# photonAlarm4.net
KiCad netlist of a schematic drawn in EAGLE
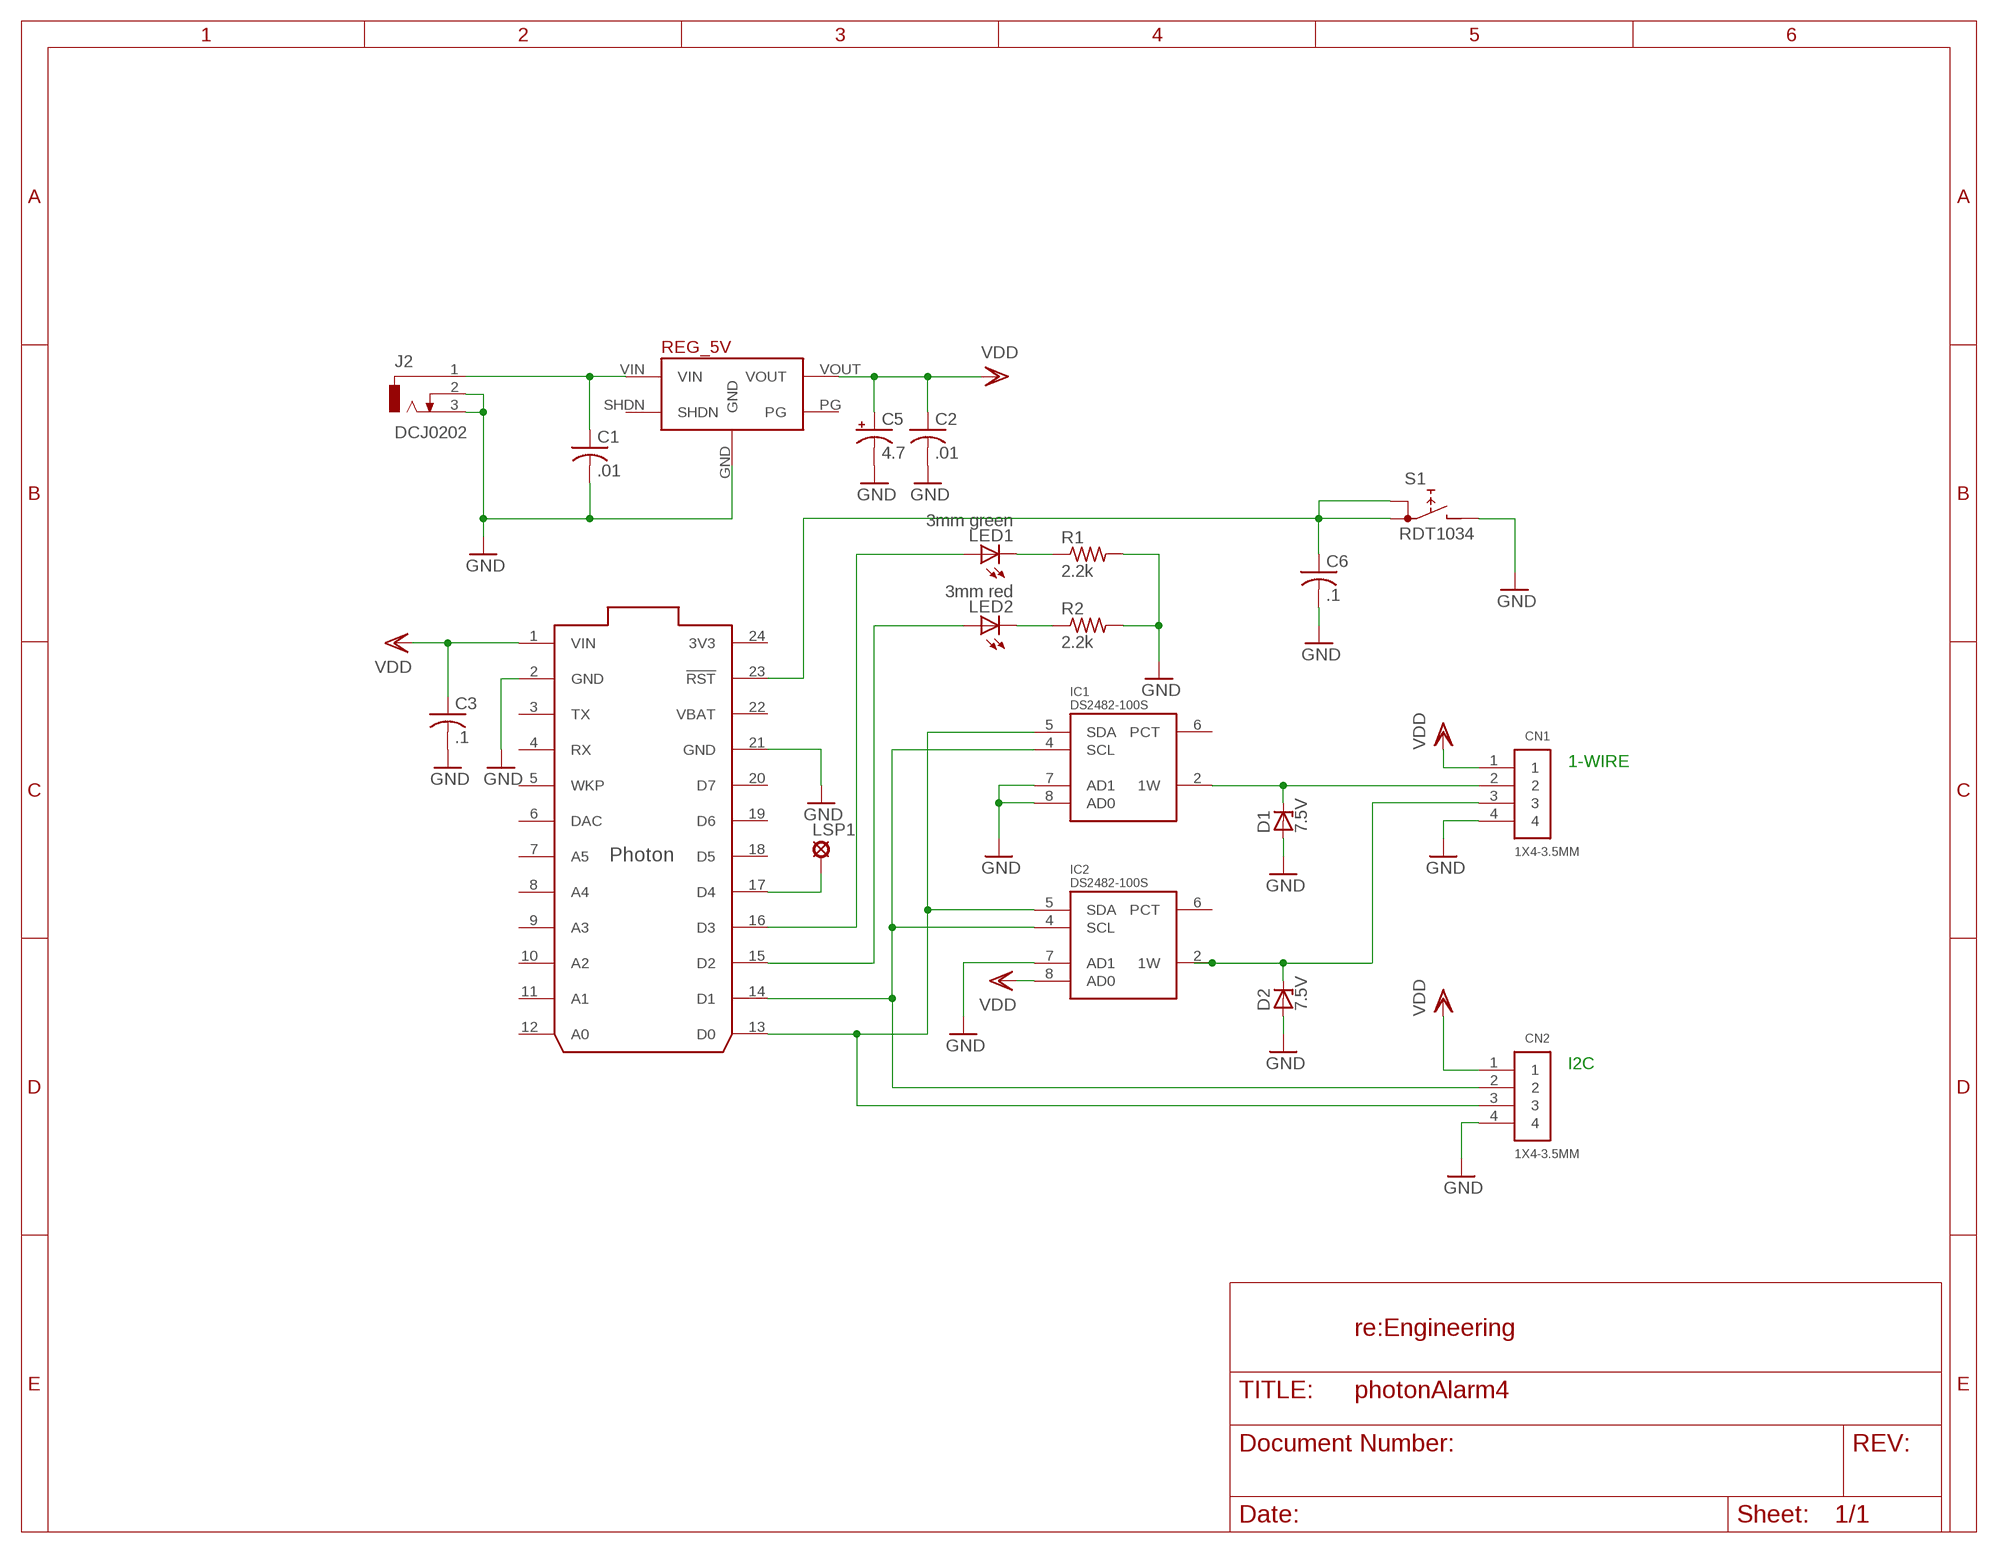
[diagram p0: schematic, sheet 1]

(export (version "E")
  (design (tool "Eeschema 10.0.6"))
  (components
    (comp (ref "C1")
      (value ".01")
      (footprint "eagle-import:C0805")
      (libsource (lib "eagle-import") (part "C-USC0805"))
    )
    (comp (ref "C2")
      (value ".01")
      (footprint "eagle-import:C0805")
      (libsource (lib "eagle-import") (part "C-USC0805"))
    )
    (comp (ref "C3")
      (value ".1")
      (footprint "eagle-import:C0805")
      (libsource (lib "eagle-import") (part "C-USC0805"))
    )
    (comp (ref "C5")
      (value "4.7")
      (footprint "eagle-import:E5-6")
      (libsource (lib "eagle-import") (part "CPOL-USE5-6"))
    )
    (comp (ref "C6")
      (value ".1")
      (footprint "eagle-import:C0805")
      (libsource (lib "eagle-import") (part "C-USC0805"))
    )
    (comp (ref "CN1")
      (value "1X4-3.5MM")
      (footprint "eagle-import:1X04-3.5MM")
      (libsource (lib "eagle-import") (part "1X4-3.5MM"))
    )
    (comp (ref "CN2")
      (value "1X4-3.5MM")
      (footprint "eagle-import:1X04-3.5MM")
      (libsource (lib "eagle-import") (part "1X4-3.5MM"))
    )
    (comp (ref "D1")
      (value "7.5V")
      (footprint "eagle-import:ZDIO-5")
      (libsource (lib "eagle-import") (part "ZENER-DIODEZD-5"))
    )
    (comp (ref "D2")
      (value "7.5V")
      (footprint "eagle-import:ZDIO-5")
      (libsource (lib "eagle-import") (part "ZENER-DIODEZD-5"))
    )
    (comp (ref "IC1")
      (value "DS2482-100S")
      (footprint "eagle-import:SO08")
      (libsource (lib "eagle-import") (part "DS2482-100S"))
    )
    (comp (ref "IC2")
      (value "DS2482-100S")
      (footprint "eagle-import:SO08")
      (libsource (lib "eagle-import") (part "DS2482-100S"))
    )
    (comp (ref "J2")
      (value "DCJ0202")
      (footprint "eagle-import:DCJ0202")
      (libsource (lib "eagle-import") (part "DCJ0202"))
    )
    (comp (ref "LED1")
      (value "3mm green")
      (footprint "eagle-import:LED5MM")
      (libsource (lib "eagle-import") (part "LED5MM"))
    )
    (comp (ref "LED2")
      (value "3mm red")
      (footprint "eagle-import:LED5MM")
      (libsource (lib "eagle-import") (part "LED5MM"))
    )
    (comp (ref "LSP1")
      (value "LSP10")
      (footprint "eagle-import:LSP10")
      (libsource (lib "eagle-import") (part "LSP10"))
    )
    (comp (ref "R1")
      (value "2.2k")
      (footprint "eagle-import:M0805")
      (libsource (lib "eagle-import") (part "R-US_M0805"))
    )
    (comp (ref "R2")
      (value "2.2k")
      (footprint "eagle-import:M0805")
      (libsource (lib "eagle-import") (part "R-US_M0805"))
    )
    (comp (ref "REG_5V")
      (value "5V_D24V10FA")
      (footprint "eagle-import:5V_D24V10F5")
      (libsource (lib "eagle-import") (part "5V_D24V10FA"))
    )
    (comp (ref "S1")
      (value "RDT1034")
      (footprint "eagle-import:RDT1034")
      (libsource (lib "eagle-import") (part "RDT1034"))
    )
    (comp (ref "U$1")
      (value "PHOTON_WITH_HEADERS")
      (footprint "eagle-import:PHOTON")
      (libsource (lib "eagle-import") (part "PHOTON_WITH_HEADERS"))
    )
  )
  (nets
    (net (code "1") (name "/3V3") (class "Default")
      (node (ref "U$1") (pin "24") (pinfunction "3V3_24") (pintype "power_in"))
    )
    (net (code "2") (name "/VBAT") (class "Default")
      (node (ref "U$1") (pin "22") (pinfunction "VBAT_22") (pintype "power_in"))
    )
    (net (code "3") (name "GND") (class "Default")
      (node (ref "C1") (pin "2") (pinfunction "2_2") (pintype "passive"))
      (node (ref "C2") (pin "2") (pinfunction "2_2") (pintype "passive"))
      (node (ref "C3") (pin "2") (pinfunction "2_2") (pintype "passive"))
      (node (ref "C5") (pin "-") (pinfunction "-_-") (pintype "passive"))
      (node (ref "C6") (pin "2") (pinfunction "2_2") (pintype "passive"))
      (node (ref "CN1") (pin "4") (pinfunction "4_4") (pintype "bidirectional"))
      (node (ref "CN2") (pin "4") (pinfunction "4_4") (pintype "bidirectional"))
      (node (ref "D1") (pin "A") (pinfunction "A_A") (pintype "passive"))
      (node (ref "D2") (pin "A") (pinfunction "A_A") (pintype "passive"))
      (node (ref "IC1") (pin "7") (pinfunction "AD1_7") (pintype "input"))
      (node (ref "IC1") (pin "8") (pinfunction "AD0_8") (pintype "input"))
      (node (ref "IC2") (pin "7") (pinfunction "AD1_7") (pintype "input"))
      (node (ref "J2") (pin "2") (pinfunction "2_2") (pintype "passive"))
      (node (ref "J2") (pin "3") (pinfunction "3_3") (pintype "passive"))
      (node (ref "R1") (pin "2") (pinfunction "2_2") (pintype "passive"))
      (node (ref "R2") (pin "2") (pinfunction "2_2") (pintype "passive"))
      (node (ref "REG_5V") (pin "GND") (pinfunction "GND_GND") (pintype "bidirectional"))
      (node (ref "S1") (pin "B") (pinfunction "B_B") (pintype "passive"))
      (node (ref "U$1") (pin "2") (pinfunction "GND_2") (pintype "power_in"))
      (node (ref "U$1") (pin "21") (pinfunction "GND_21") (pintype "power_in"))
    )
    (net (code "4") (name "Net-(C1-Pad1)") (class "Default")
      (node (ref "C1") (pin "1") (pinfunction "1_1") (pintype "passive"))
      (node (ref "J2") (pin "1") (pinfunction "1_1") (pintype "passive"))
      (node (ref "REG_5V") (pin "VIN") (pinfunction "VIN_VIN") (pintype "bidirectional"))
    )
    (net (code "5") (name "Net-(IC1A-1W)") (class "Default")
      (node (ref "CN1") (pin "2") (pinfunction "2_2") (pintype "bidirectional"))
      (node (ref "D1") (pin "C") (pinfunction "C_C") (pintype "passive"))
      (node (ref "IC1") (pin "2") (pinfunction "1W_2") (pintype "open_collector"))
    )
    (net (code "6") (name "Net-(IC1A-SCL)") (class "Default")
      (node (ref "CN2") (pin "2") (pinfunction "2_2") (pintype "bidirectional"))
      (node (ref "IC1") (pin "4") (pinfunction "SCL_4") (pintype "input"))
      (node (ref "IC2") (pin "4") (pinfunction "SCL_4") (pintype "input"))
      (node (ref "U$1") (pin "14") (pinfunction "D1_14") (pintype "bidirectional"))
    )
    (net (code "7") (name "Net-(IC1A-SDA)") (class "Default")
      (node (ref "CN2") (pin "3") (pinfunction "3_3") (pintype "bidirectional"))
      (node (ref "IC1") (pin "5") (pinfunction "SDA_5") (pintype "bidirectional"))
      (node (ref "IC2") (pin "5") (pinfunction "SDA_5") (pintype "bidirectional"))
      (node (ref "U$1") (pin "13") (pinfunction "D0_13") (pintype "bidirectional"))
    )
    (net (code "8") (name "Net-(IC2A-1W)") (class "Default")
      (node (ref "CN1") (pin "3") (pinfunction "3_3") (pintype "bidirectional"))
      (node (ref "D2") (pin "C") (pinfunction "C_C") (pintype "passive"))
      (node (ref "IC2") (pin "2") (pinfunction "1W_2") (pintype "open_collector"))
    )
    (net (code "9") (name "Net-(LED1-C)") (class "Default")
      (node (ref "LED1") (pin "K") (pinfunction "C_K") (pintype "passive"))
      (node (ref "R1") (pin "1") (pinfunction "1_1") (pintype "passive"))
    )
    (net (code "10") (name "Net-(LED2-C)") (class "Default")
      (node (ref "LED2") (pin "K") (pinfunction "C_K") (pintype "passive"))
      (node (ref "R2") (pin "1") (pinfunction "1_1") (pintype "passive"))
    )
    (net (code "11") (name "Net-(U$1-D2)") (class "Default")
      (node (ref "LED2") (pin "A") (pinfunction "A_A") (pintype "passive"))
      (node (ref "U$1") (pin "15") (pinfunction "D2_15") (pintype "bidirectional"))
    )
    (net (code "12") (name "Net-(U$1-D3)") (class "Default")
      (node (ref "LED1") (pin "A") (pinfunction "A_A") (pintype "passive"))
      (node (ref "U$1") (pin "16") (pinfunction "D3_16") (pintype "bidirectional"))
    )
    (net (code "13") (name "Net-(U$1-D4)") (class "Default")
      (node (ref "LSP1") (pin "MP") (pinfunction "MP_MP") (pintype "passive"))
      (node (ref "U$1") (pin "17") (pinfunction "D4_17") (pintype "bidirectional"))
    )
    (net (code "14") (name "Net-(U$1-~{RST})") (class "Default")
      (node (ref "C6") (pin "1") (pinfunction "1_1") (pintype "passive"))
      (node (ref "S1") (pin "A") (pinfunction "A_A") (pintype "passive"))
      (node (ref "S1") (pin "A1") (pinfunction "A1_A1") (pintype "passive"))
      (node (ref "U$1") (pin "23") (pinfunction "~{RST}_23") (pintype "bidirectional"))
    )
    (net (code "15") (name "VDD") (class "Default")
      (node (ref "C2") (pin "1") (pinfunction "1_1") (pintype "passive"))
      (node (ref "C3") (pin "1") (pinfunction "1_1") (pintype "passive"))
      (node (ref "C5") (pin "+") (pinfunction "+_+") (pintype "passive"))
      (node (ref "CN1") (pin "1") (pinfunction "1_1") (pintype "bidirectional"))
      (node (ref "CN2") (pin "1") (pinfunction "1_1") (pintype "bidirectional"))
      (node (ref "IC2") (pin "8") (pinfunction "AD0_8") (pintype "input"))
      (node (ref "REG_5V") (pin "VOUT") (pinfunction "VOUT_VOUT") (pintype "bidirectional"))
      (node (ref "U$1") (pin "1") (pinfunction "VIN_1") (pintype "power_in"))
    )
    (net (code "16") (name "unconnected-(IC1A-PCT-Pad6)") (class "Default")
      (node (ref "IC1") (pin "6") (pinfunction "PCT_6") (pintype "output"))
    )
    (net (code "17") (name "unconnected-(IC2A-PCT-Pad6)") (class "Default")
      (node (ref "IC2") (pin "6") (pinfunction "PCT_6") (pintype "output"))
    )
    (net (code "18") (name "unconnected-(REG_5V-PadPG)") (class "Default")
      (node (ref "REG_5V") (pin "PG") (pinfunction "PG_PG") (pintype "bidirectional"))
    )
    (net (code "19") (name "unconnected-(REG_5V-PadSHDN)") (class "Default")
      (node (ref "REG_5V") (pin "SHDN") (pinfunction "SHDN_SHDN") (pintype "bidirectional"))
    )
    (net (code "20") (name "unconnected-(U$1-A0-Pad12)") (class "Default")
      (node (ref "U$1") (pin "12") (pinfunction "A0_12") (pintype "bidirectional"))
    )
    (net (code "21") (name "unconnected-(U$1-A1-Pad11)") (class "Default")
      (node (ref "U$1") (pin "11") (pinfunction "A1_11") (pintype "bidirectional"))
    )
    (net (code "22") (name "unconnected-(U$1-A2-Pad10)") (class "Default")
      (node (ref "U$1") (pin "10") (pinfunction "A2_10") (pintype "bidirectional"))
    )
    (net (code "23") (name "unconnected-(U$1-A3-Pad9)") (class "Default")
      (node (ref "U$1") (pin "9") (pinfunction "A3_9") (pintype "bidirectional"))
    )
    (net (code "24") (name "unconnected-(U$1-A4-Pad8)") (class "Default")
      (node (ref "U$1") (pin "8") (pinfunction "A4_8") (pintype "bidirectional"))
    )
    (net (code "25") (name "unconnected-(U$1-A5-Pad7)") (class "Default")
      (node (ref "U$1") (pin "7") (pinfunction "A5_7") (pintype "bidirectional"))
    )
    (net (code "26") (name "unconnected-(U$1-D5-Pad18)") (class "Default")
      (node (ref "U$1") (pin "18") (pinfunction "D5_18") (pintype "bidirectional"))
    )
    (net (code "27") (name "unconnected-(U$1-D6-Pad19)") (class "Default")
      (node (ref "U$1") (pin "19") (pinfunction "D6_19") (pintype "bidirectional"))
    )
    (net (code "28") (name "unconnected-(U$1-D7-Pad20)") (class "Default")
      (node (ref "U$1") (pin "20") (pinfunction "D7_20") (pintype "bidirectional"))
    )
    (net (code "29") (name "unconnected-(U$1-DAC-Pad6)") (class "Default")
      (node (ref "U$1") (pin "6") (pinfunction "DAC_6") (pintype "bidirectional"))
    )
    (net (code "30") (name "unconnected-(U$1-RX-Pad4)") (class "Default")
      (node (ref "U$1") (pin "4") (pinfunction "RX_4") (pintype "bidirectional"))
    )
    (net (code "31") (name "unconnected-(U$1-TX-Pad3)") (class "Default")
      (node (ref "U$1") (pin "3") (pinfunction "TX_3") (pintype "bidirectional"))
    )
    (net (code "32") (name "unconnected-(U$1-WKP-Pad5)") (class "Default")
      (node (ref "U$1") (pin "5") (pinfunction "WKP_5") (pintype "bidirectional"))
    )
  )
)
